# Mutli-Stepper-Driver_Rev_2.net
KiCad netlist of a schematic drawn in EAGLE
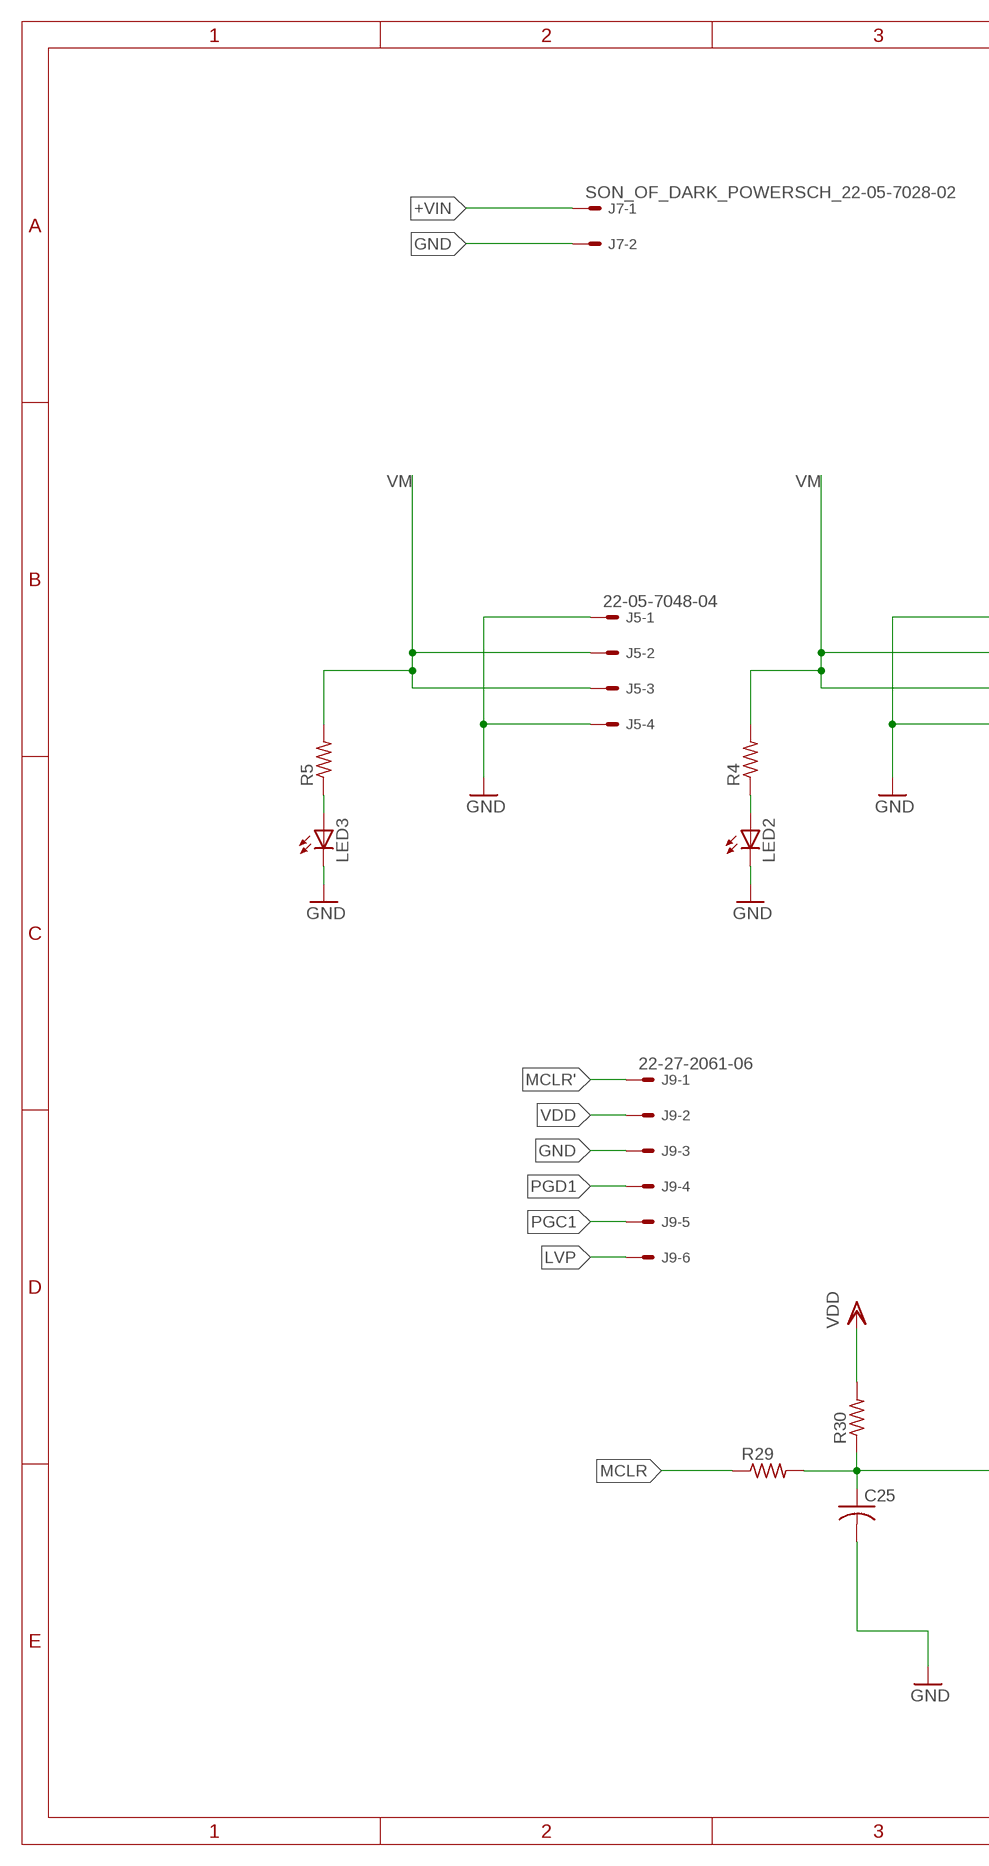
[diagram p0: schematic, sheet 1, part 1 of 2]
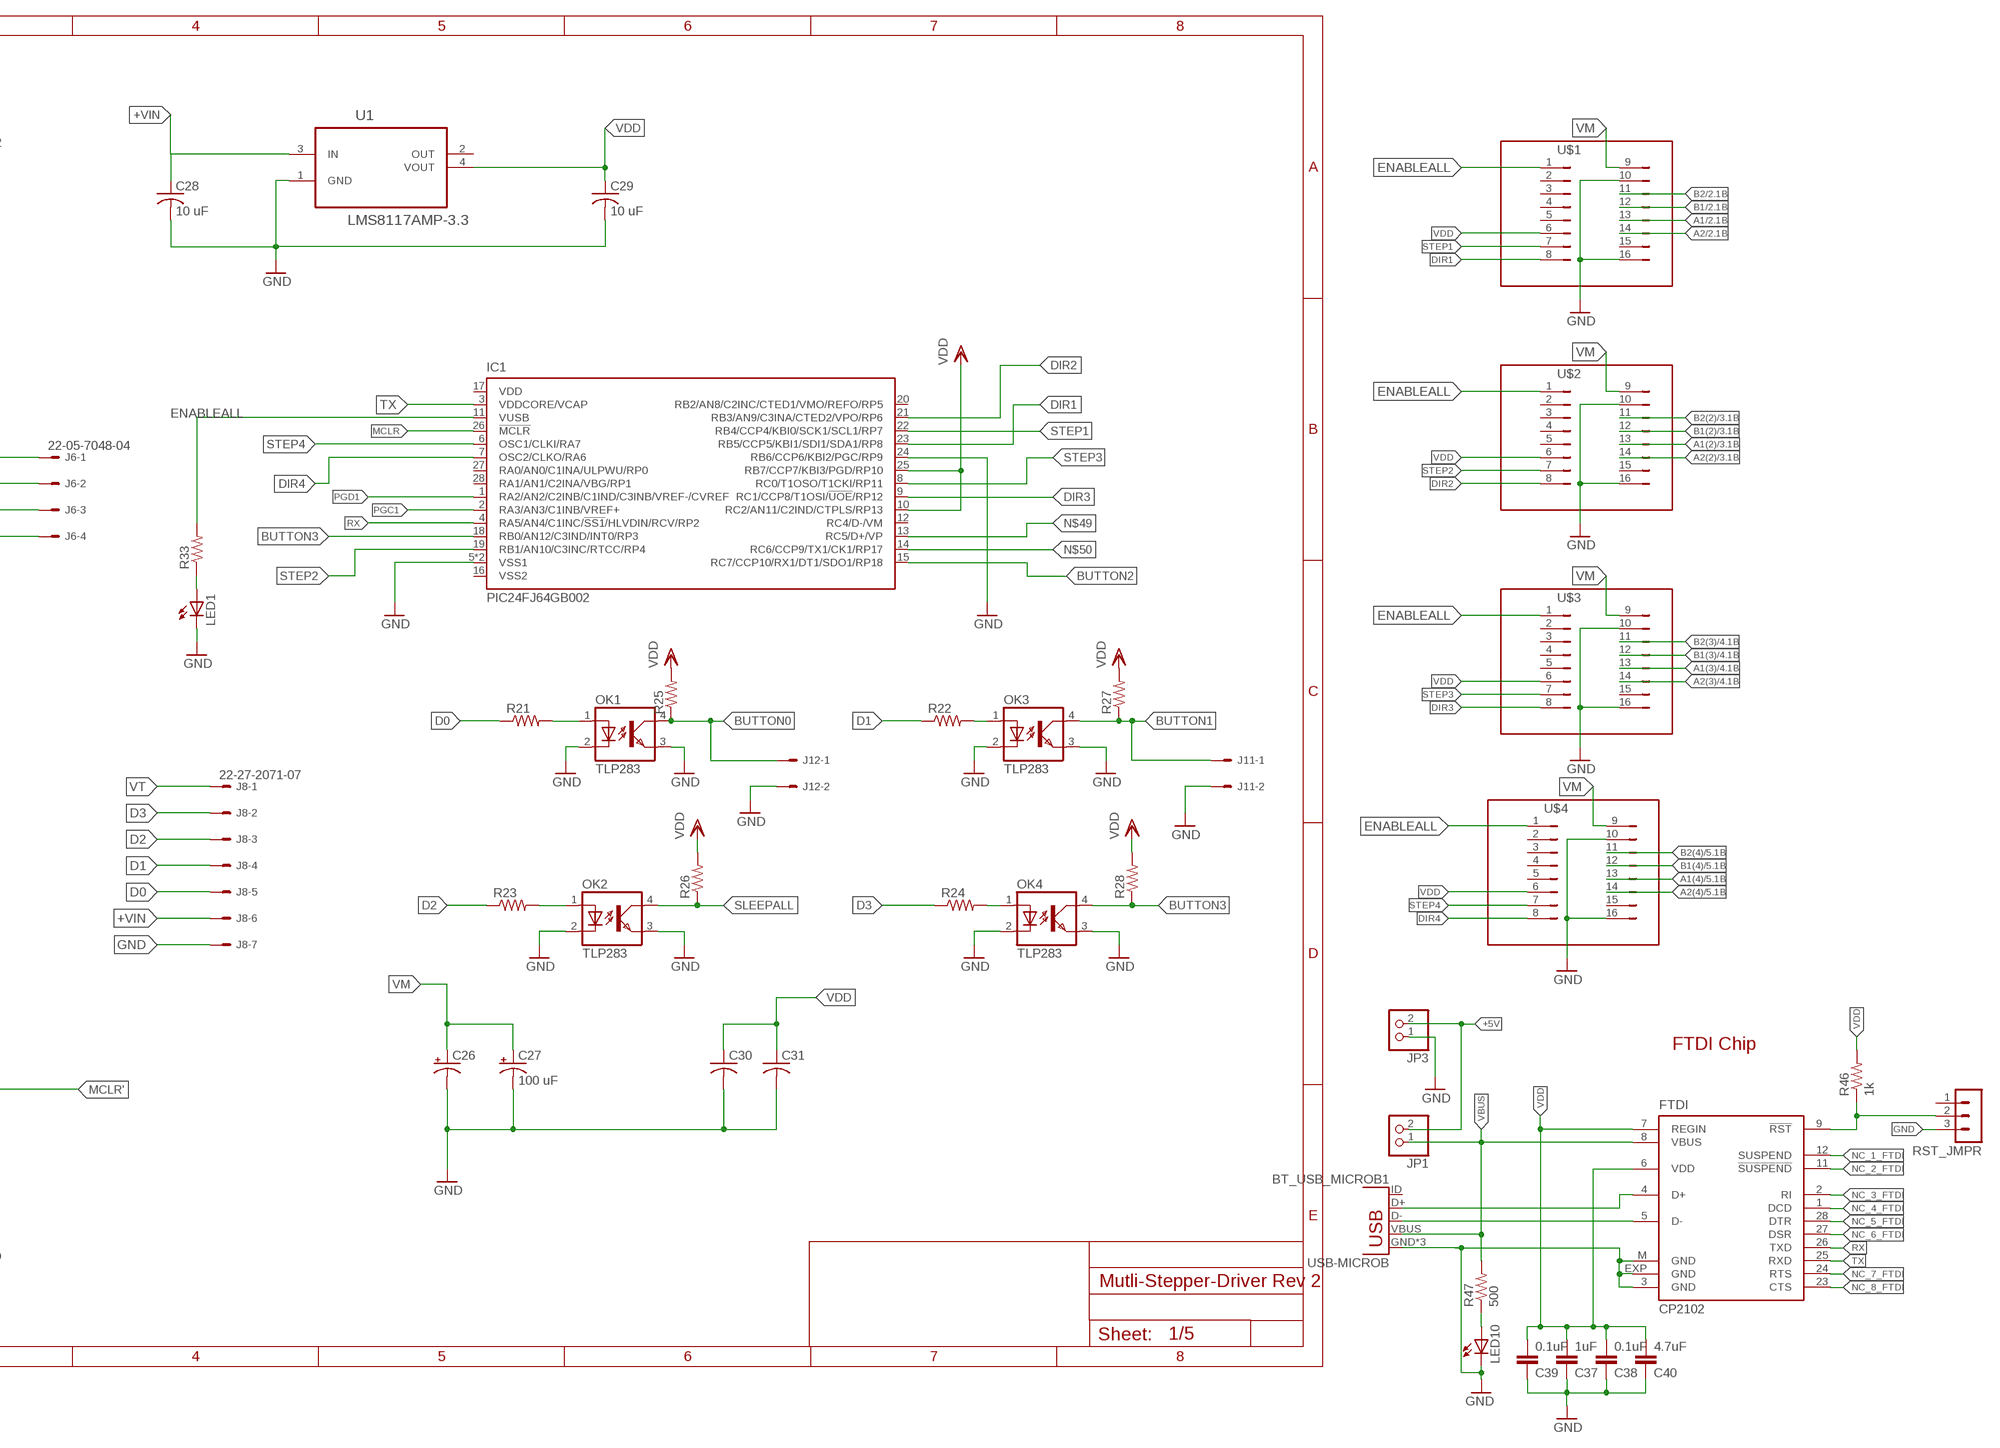
[diagram p1: schematic, sheet 1, part 2 of 2]
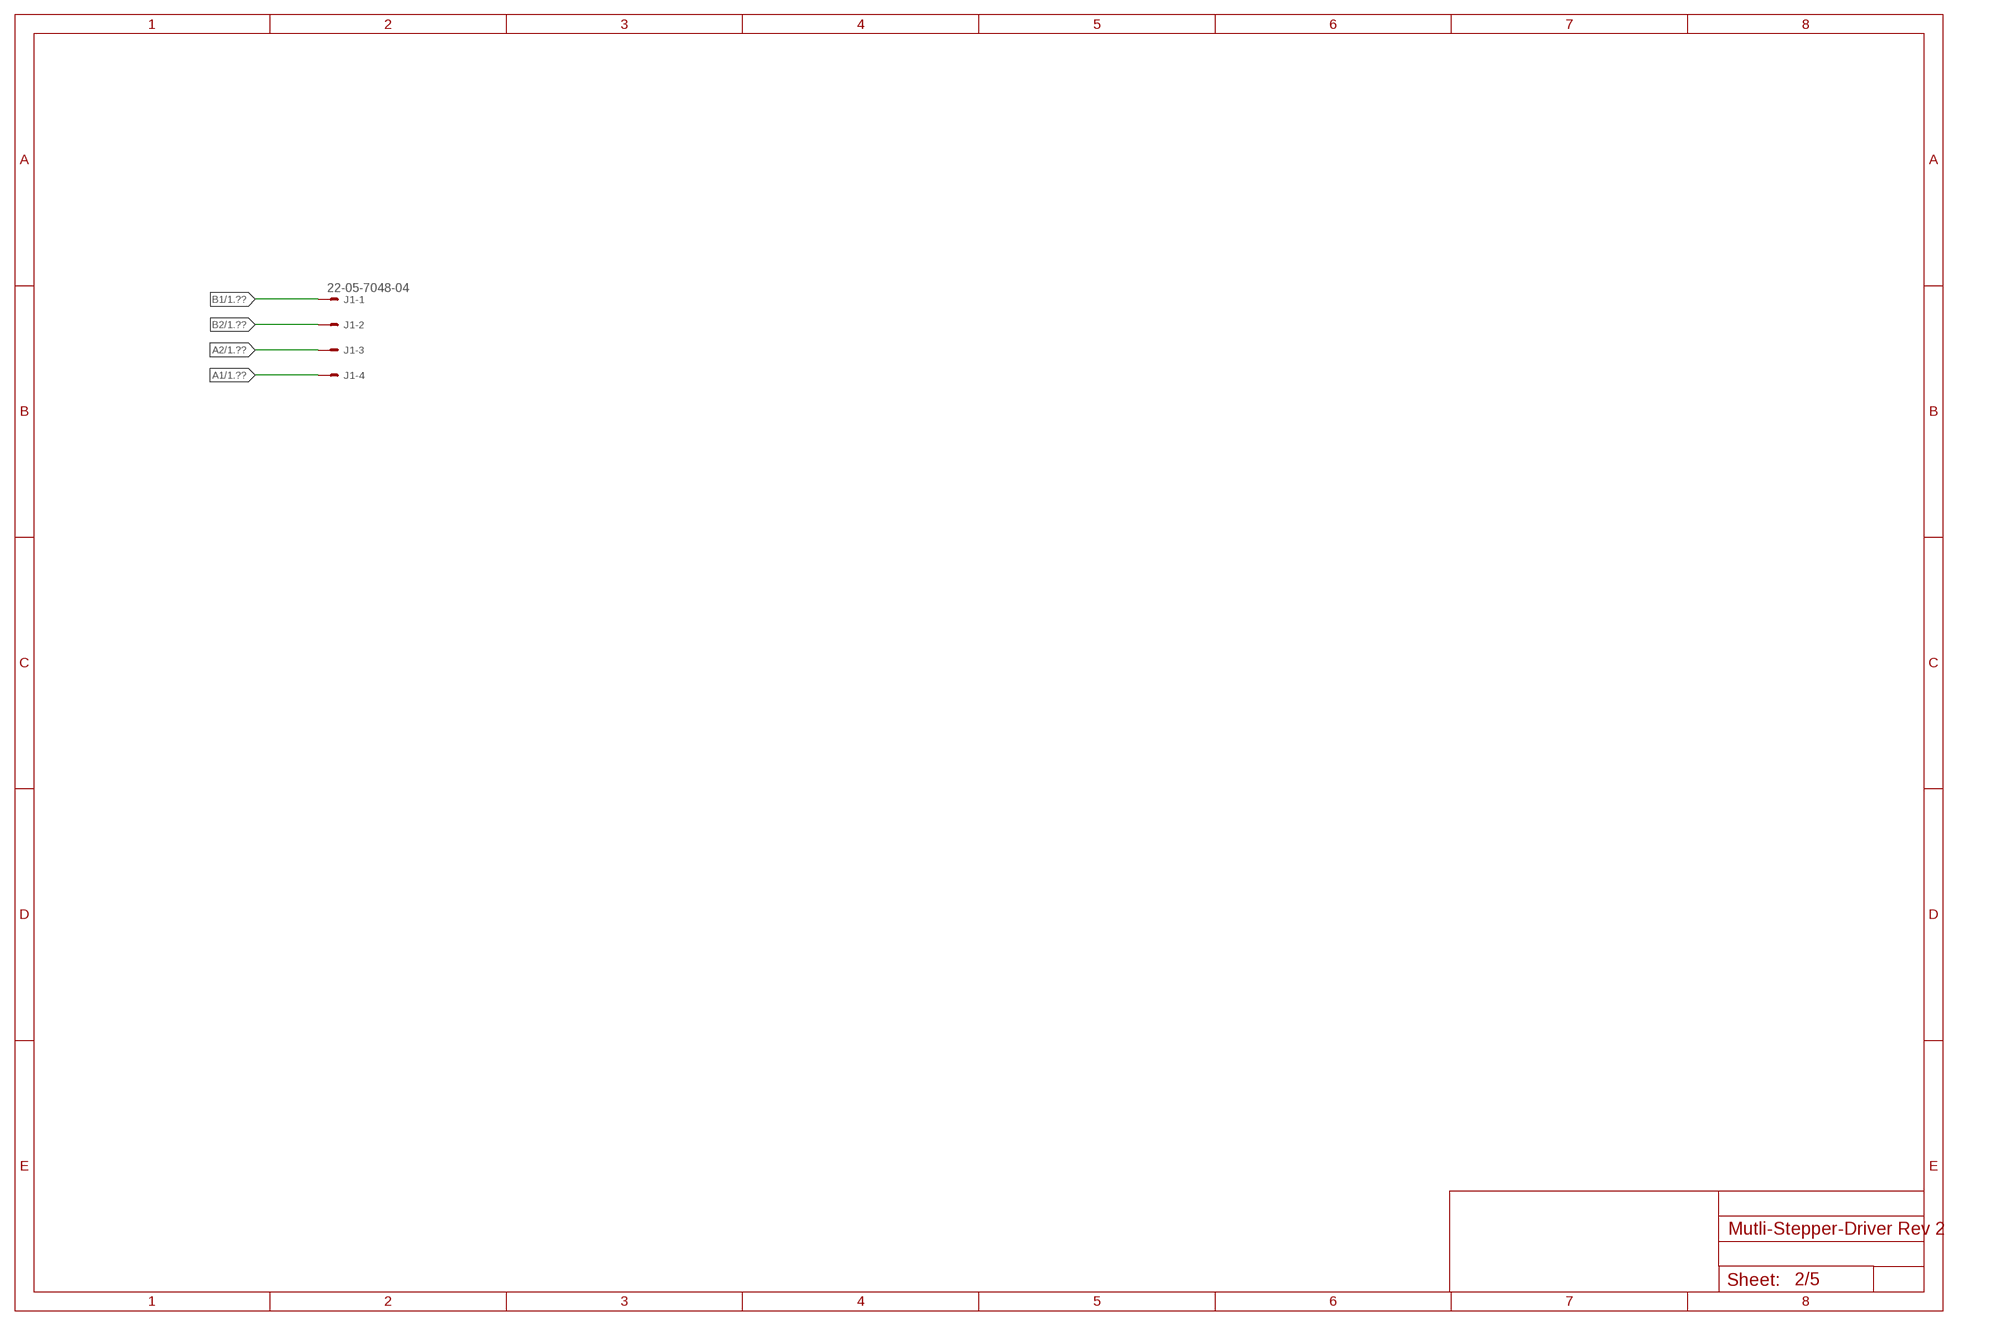
[diagram p2: schematic, sheet 2]
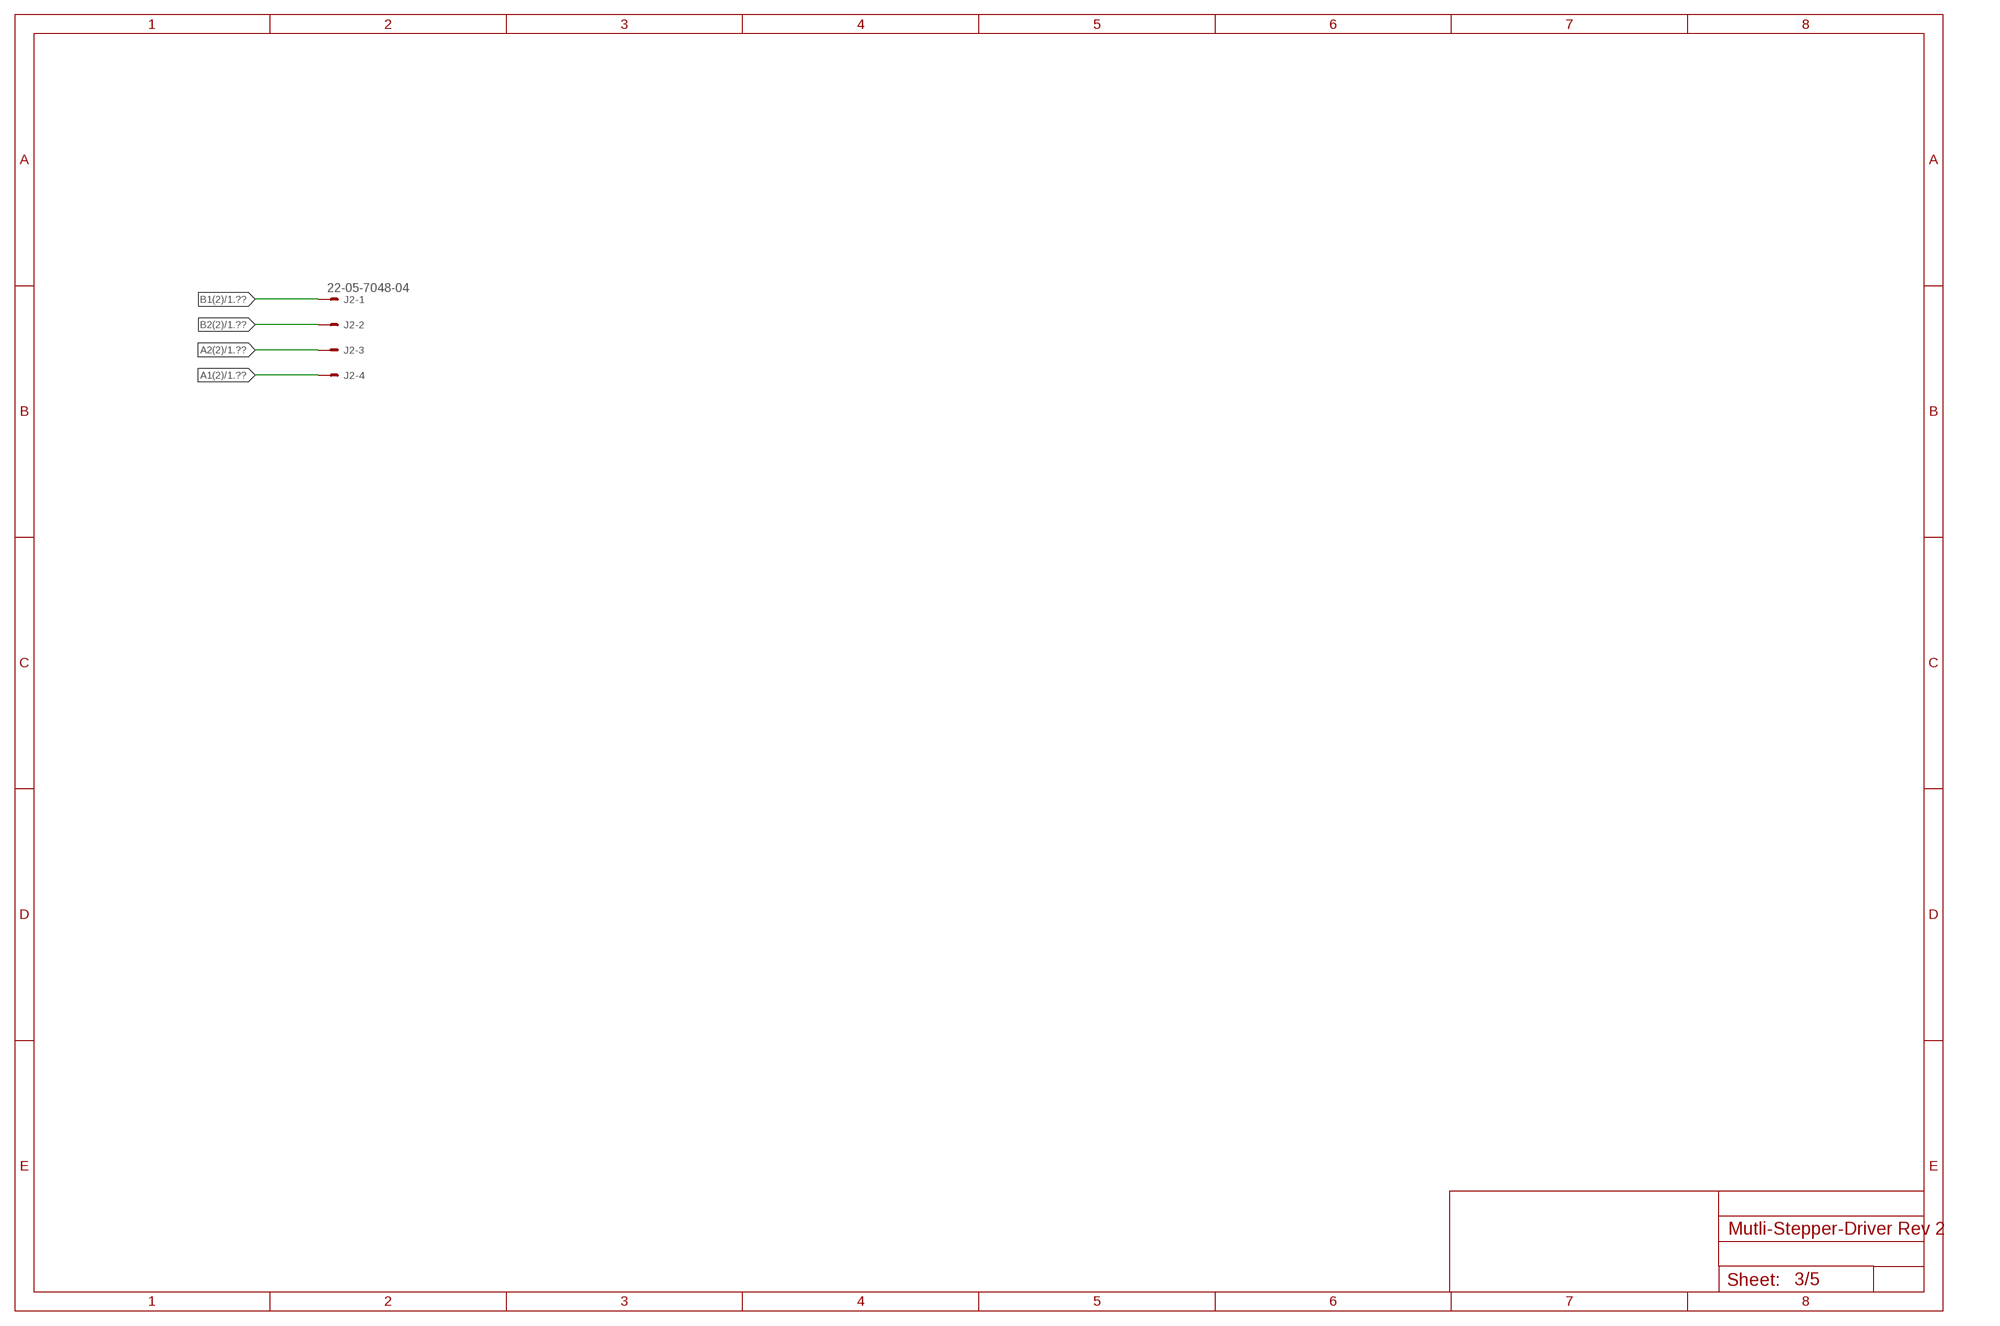
[diagram p3: schematic, sheet 3]
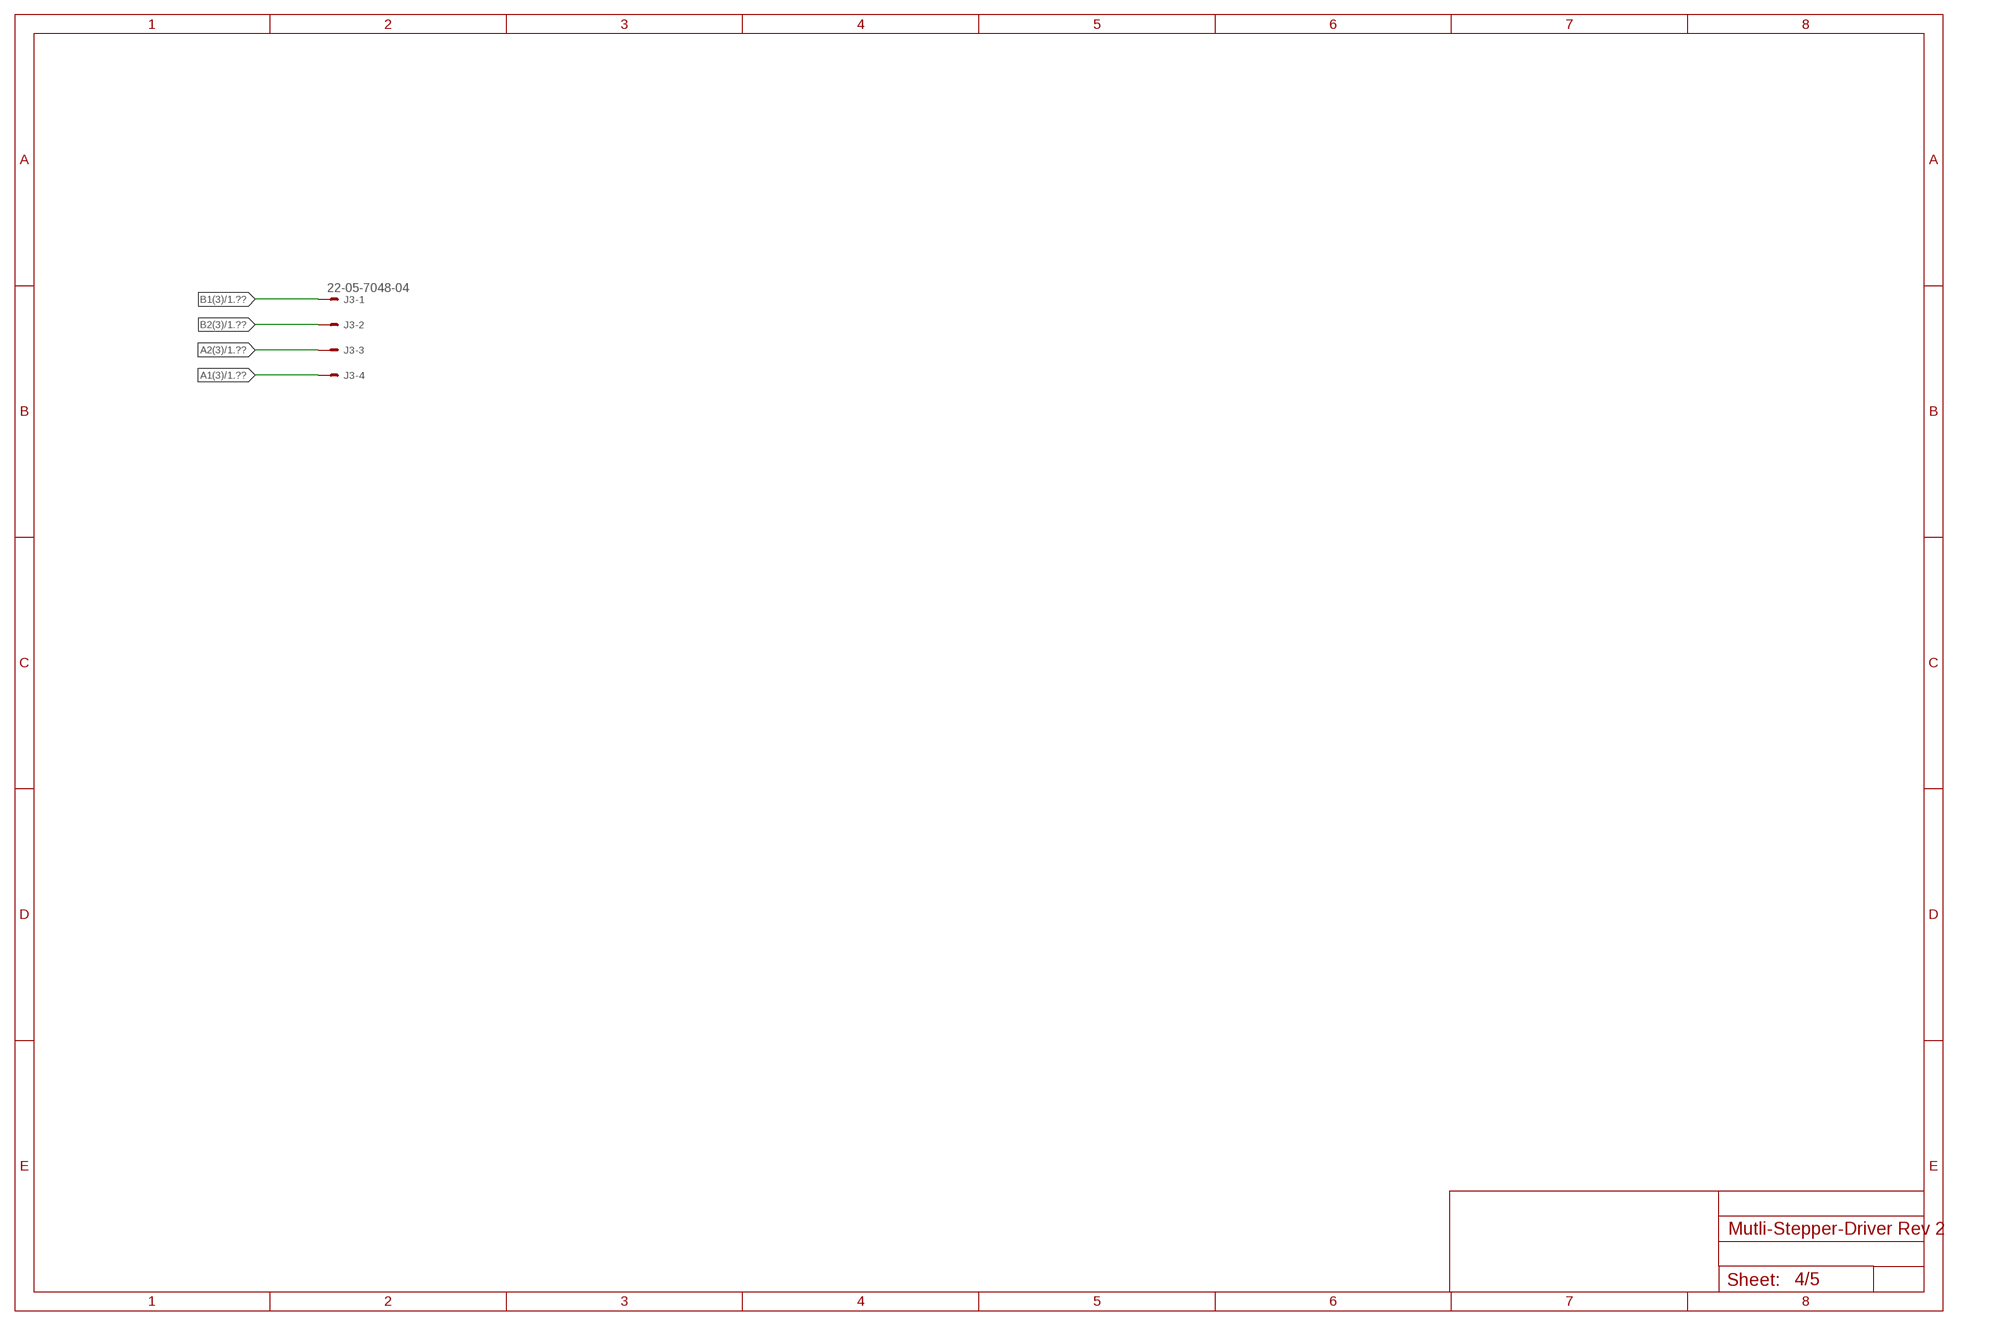
[diagram p4: schematic, sheet 4]
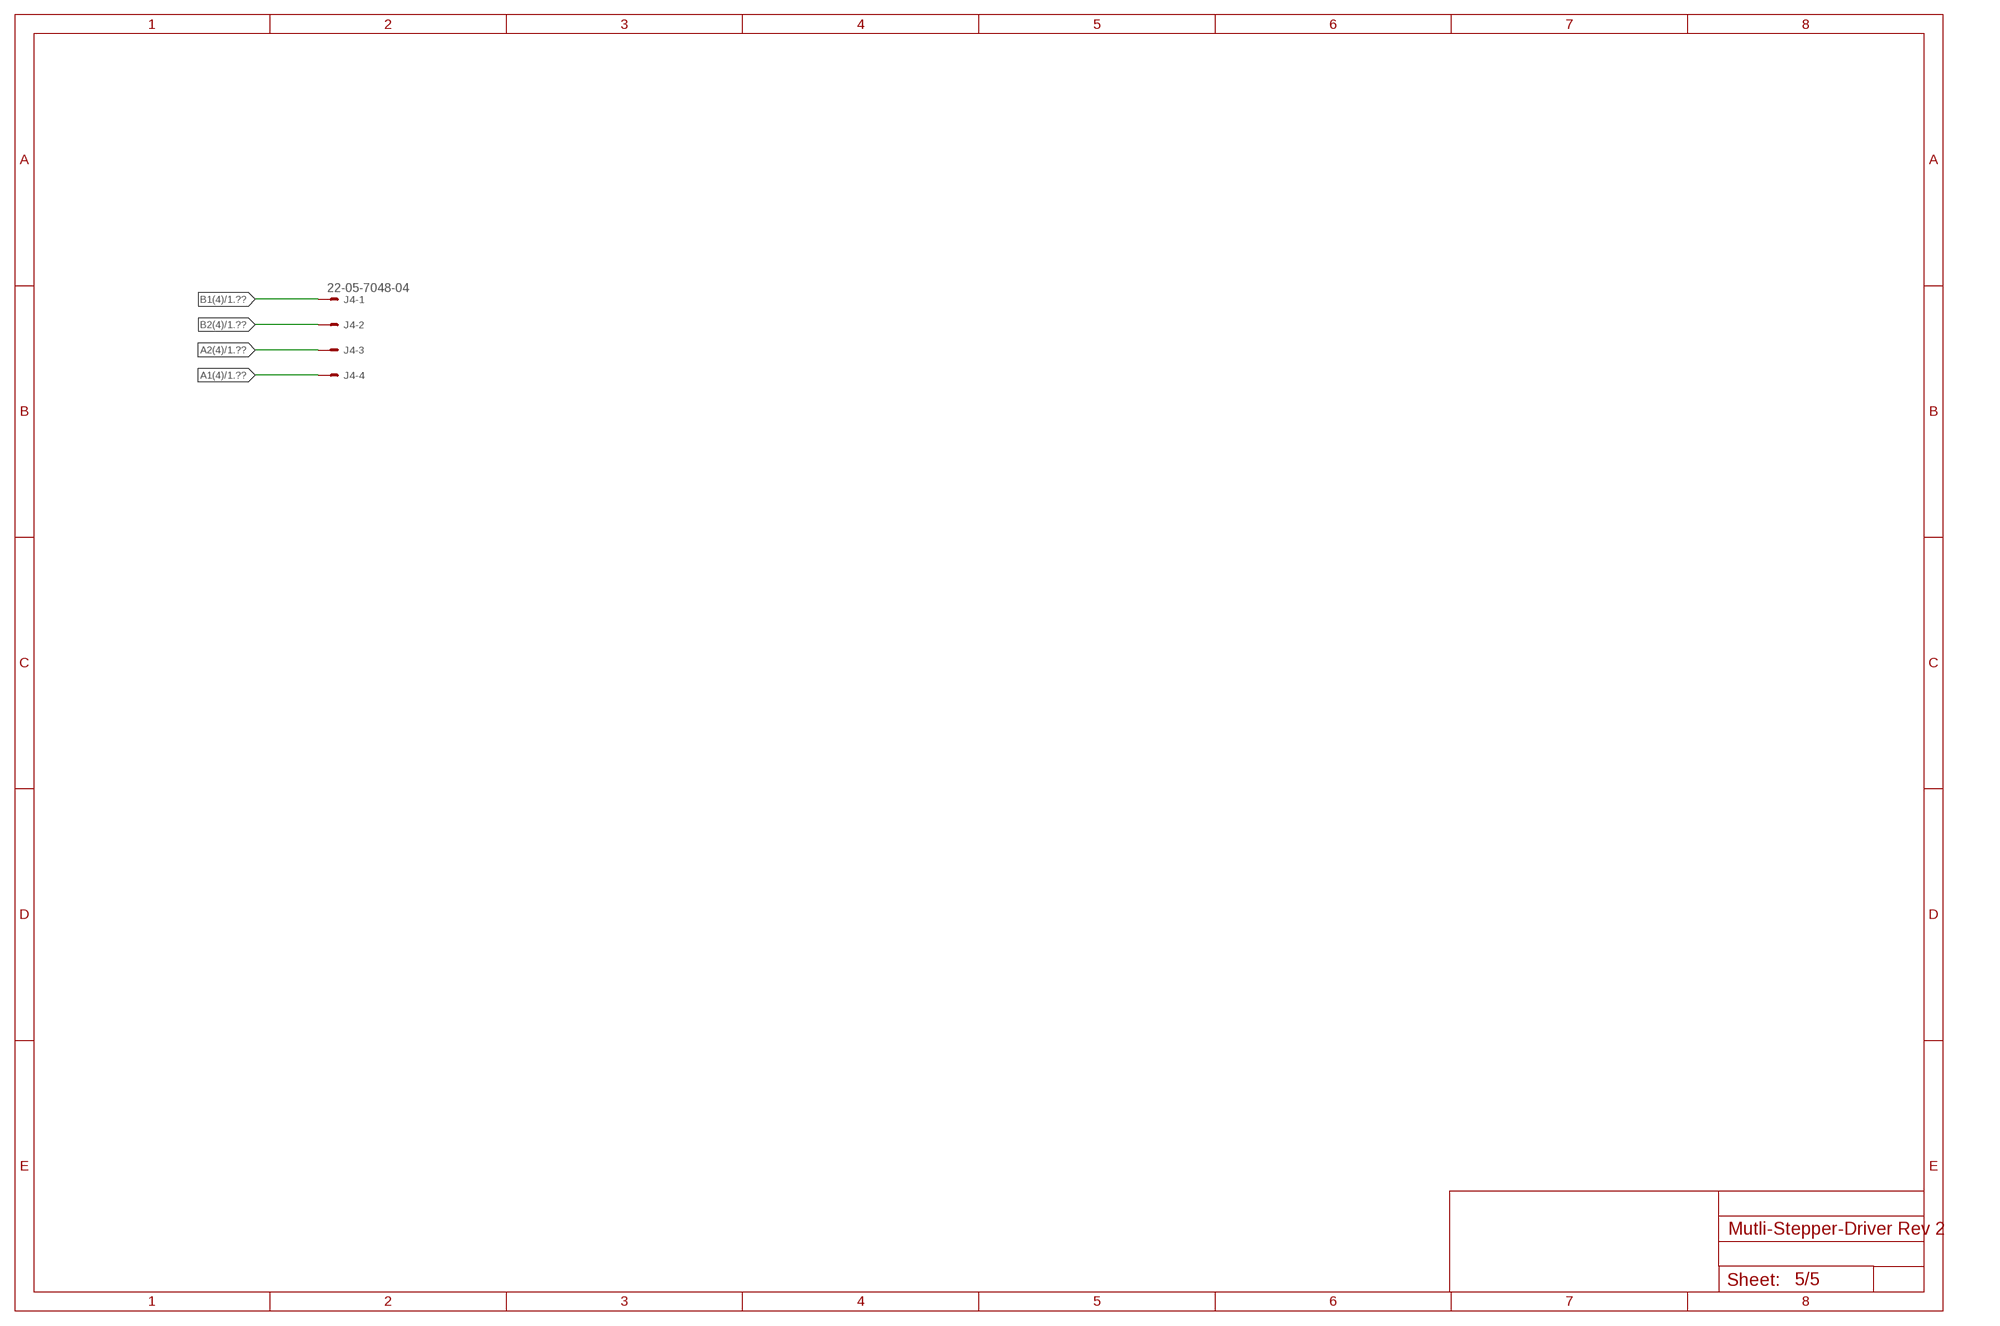
[diagram p5: schematic, sheet 5]

(export (version "E")
  (design (tool "Eeschema 10.0.6"))
  (components
    (comp (ref "BT_USB_MICROB1")
      (value "USB-MICROB")
      (footprint "eagle-import:USB-MICROB")
      (libsource (lib "eagle-import") (part "USB-MICROB"))
    )
    (comp (ref "C25")
      (value "C-USC0805")
      (footprint "eagle-import:C0805")
      (libsource (lib "eagle-import") (part "C-USC0805"))
    )
    (comp (ref "C26")
      (value "CPOL-USCT7343")
      (footprint "eagle-import:CT7343")
      (libsource (lib "eagle-import") (part "CPOL-USCT7343"))
    )
    (comp (ref "C27")
      (value "100 uF")
      (footprint "eagle-import:CT7343")
      (libsource (lib "eagle-import") (part "CPOL-USCT7343"))
    )
    (comp (ref "C28")
      (value "10 uF")
      (footprint "eagle-import:C3216")
      (libsource (lib "eagle-import") (part "C-USC3216"))
    )
    (comp (ref "C29")
      (value "10 uF")
      (footprint "eagle-import:C3216")
      (libsource (lib "eagle-import") (part "C-USC3216"))
    )
    (comp (ref "C30")
      (value "C-USC0805")
      (footprint "eagle-import:C0805")
      (libsource (lib "eagle-import") (part "C-USC0805"))
    )
    (comp (ref "C31")
      (value "C-USC0805")
      (footprint "eagle-import:C0805")
      (libsource (lib "eagle-import") (part "C-USC0805"))
    )
    (comp (ref "C37")
      (value "1uF")
      (footprint "eagle-import:C0805")
      (libsource (lib "eagle-import") (part "C-EUC0805"))
    )
    (comp (ref "C38")
      (value "0.1uF")
      (footprint "eagle-import:C0805")
      (libsource (lib "eagle-import") (part "C-EUC0805"))
    )
    (comp (ref "C39")
      (value "0.1uF")
      (footprint "eagle-import:C0805")
      (libsource (lib "eagle-import") (part "C-EUC0805"))
    )
    (comp (ref "C40")
      (value "4.7uF")
      (footprint "eagle-import:C0805")
      (libsource (lib "eagle-import") (part "C-EUC0805"))
    )
    (comp (ref "FTDI")
      (value "CP2102")
      (footprint "eagle-import:MLP28")
      (fields (field (name "MF") "FARNELL") (field (name "MPN") "CP2102-GM"))
      (libsource (lib "eagle-import") (part "CP2102"))
    )
    (comp (ref "IC1")
      (value "PIC24FJ64GB002")
      (footprint "eagle-import:MICROCHIP_QFN28-ML_6X6MM")
      (libsource (lib "eagle-import") (part "MICROCHIP_PIC18F2J53ML"))
    )
    (comp (ref "J5")
      (value "22-05-7048-04")
      (footprint "eagle-import:7395-04")
      (libsource (lib "eagle-import") (part "22-?-0405-7048"))
    )
    (comp (ref "J6")
      (value "22-05-7048-04")
      (footprint "eagle-import:7395-04")
      (libsource (lib "eagle-import") (part "22-?-0405-7048"))
    )
    (comp (ref "J7")
      (value "SON_OF_DARK_POWERSCH_22-05-7028-02")
      (footprint "eagle-import:SON_OF_DARK_POWERSCH_7395-02")
      (libsource (lib "eagle-import") (part "SON_OF_DARK_POWERSCH_22-?-0205-7028"))
    )
    (comp (ref "J8")
      (value "22-27-2071-07")
      (footprint "eagle-import:6410-07")
      (libsource (lib "eagle-import") (part "22-?-0727-2071"))
    )
    (comp (ref "J9")
      (value "22-27-2061-06")
      (footprint "eagle-import:6410-06")
      (libsource (lib "eagle-import") (part "22-?-0627-2061"))
    )
    (comp (ref "J11")
      (value "SON_OF_DARK_POWERSCH_22-05-7028-02")
      (footprint "eagle-import:SON_OF_DARK_POWERSCH_7395-02")
      (libsource (lib "eagle-import") (part "SON_OF_DARK_POWERSCH_22-?-0205-7028"))
    )
    (comp (ref "J12")
      (value "SON_OF_DARK_POWERSCH_22-05-7028-02")
      (footprint "eagle-import:SON_OF_DARK_POWERSCH_7395-02")
      (libsource (lib "eagle-import") (part "SON_OF_DARK_POWERSCH_22-?-0205-7028"))
    )
    (comp (ref "JP1")
      (value "PINHD-1X2")
      (footprint "eagle-import:1X02")
      (libsource (lib "eagle-import") (part "PINHD-1X2"))
    )
    (comp (ref "JP3")
      (value "PINHD-1X2")
      (footprint "eagle-import:1X02")
      (libsource (lib "eagle-import") (part "PINHD-1X2"))
    )
    (comp (ref "LED1")
      (value "LEDCHIPLED_0805")
      (footprint "eagle-import:CHIPLED_0805")
      (libsource (lib "eagle-import") (part "led_LEDCHIPLED_0805"))
    )
    (comp (ref "LED2")
      (value "LEDCHIPLED_0805")
      (footprint "eagle-import:CHIPLED_0805")
      (libsource (lib "eagle-import") (part "led_LEDCHIPLED_0805"))
    )
    (comp (ref "LED3")
      (value "LEDCHIPLED_0805")
      (footprint "eagle-import:CHIPLED_0805")
      (libsource (lib "eagle-import") (part "led_LEDCHIPLED_0805"))
    )
    (comp (ref "LED10")
      (value "LEDSML0603")
      (footprint "eagle-import:SML0603")
      (libsource (lib "eagle-import") (part "LEDSML0603"))
    )
    (comp (ref "OK1")
      (value "TLP283")
      (footprint "eagle-import:MINI-FLAT-4")
      (libsource (lib "eagle-import") (part "TLP283"))
    )
    (comp (ref "OK2")
      (value "TLP283")
      (footprint "eagle-import:MINI-FLAT-4")
      (libsource (lib "eagle-import") (part "TLP283"))
    )
    (comp (ref "OK3")
      (value "TLP283")
      (footprint "eagle-import:MINI-FLAT-4")
      (libsource (lib "eagle-import") (part "TLP283"))
    )
    (comp (ref "OK4")
      (value "TLP283")
      (footprint "eagle-import:MINI-FLAT-4")
      (libsource (lib "eagle-import") (part "TLP283"))
    )
    (comp (ref "R4")
      (value "R-US_R0805")
      (footprint "eagle-import:R0805")
      (libsource (lib "eagle-import") (part "R-US_R0805"))
    )
    (comp (ref "R5")
      (value "R-US_R0805")
      (footprint "eagle-import:R0805")
      (libsource (lib "eagle-import") (part "R-US_R0805"))
    )
    (comp (ref "R21")
      (value "R-US_R0805")
      (footprint "eagle-import:R0805")
      (libsource (lib "eagle-import") (part "R-US_R0805"))
    )
    (comp (ref "R22")
      (value "R-US_R0805")
      (footprint "eagle-import:R0805")
      (libsource (lib "eagle-import") (part "R-US_R0805"))
    )
    (comp (ref "R23")
      (value "R-US_R0805")
      (footprint "eagle-import:R0805")
      (libsource (lib "eagle-import") (part "R-US_R0805"))
    )
    (comp (ref "R24")
      (value "R-US_R0805")
      (footprint "eagle-import:R0805")
      (libsource (lib "eagle-import") (part "R-US_R0805"))
    )
    (comp (ref "R25")
      (value "R-US_R0805")
      (footprint "eagle-import:R0805")
      (libsource (lib "eagle-import") (part "R-US_R0805"))
    )
    (comp (ref "R26")
      (value "R-US_R0805")
      (footprint "eagle-import:R0805")
      (libsource (lib "eagle-import") (part "R-US_R0805"))
    )
    (comp (ref "R27")
      (value "R-US_R0805")
      (footprint "eagle-import:R0805")
      (libsource (lib "eagle-import") (part "R-US_R0805"))
    )
    (comp (ref "R28")
      (value "R-US_R0805")
      (footprint "eagle-import:R0805")
      (libsource (lib "eagle-import") (part "R-US_R0805"))
    )
    (comp (ref "R29")
      (value "R-US_R0805")
      (footprint "eagle-import:R0805")
      (libsource (lib "eagle-import") (part "R-US_R0805"))
    )
    (comp (ref "R30")
      (value "R-US_R0805")
      (footprint "eagle-import:R0805")
      (libsource (lib "eagle-import") (part "R-US_R0805"))
    )
    (comp (ref "R33")
      (value "R-US_R0805")
      (footprint "eagle-import:R0805")
      (libsource (lib "eagle-import") (part "R-US_R0805"))
    )
    (comp (ref "R46")
      (value "1k")
      (footprint "eagle-import:R0805")
      (libsource (lib "eagle-import") (part "resistor_R-US_R0805"))
    )
    (comp (ref "R47")
      (value "500")
      (footprint "eagle-import:R0805")
      (libsource (lib "eagle-import") (part "resistor_R-US_R0805"))
    )
    (comp (ref "RST_JMPR")
      (value "MA03-1")
      (footprint "eagle-import:MA03-1")
      (libsource (lib "eagle-import") (part "MA03-1"))
    )
    (comp (ref "U$1")
      (value "DRIVER")
      (footprint "eagle-import:6410-08")
      (libsource (lib "eagle-import") (part "DRIVER"))
    )
    (comp (ref "U$2")
      (value "DRIVER")
      (footprint "eagle-import:6410-08")
      (libsource (lib "eagle-import") (part "DRIVER"))
    )
    (comp (ref "U$3")
      (value "DRIVER")
      (footprint "eagle-import:6410-08")
      (libsource (lib "eagle-import") (part "DRIVER"))
    )
    (comp (ref "U$4")
      (value "DRIVER")
      (footprint "eagle-import:6410-08")
      (libsource (lib "eagle-import") (part "DRIVER"))
    )
    (comp (ref "U1")
      (value "LMS8117AMP-3.3")
      (footprint "eagle-import:NSC-LMS8117AMP_SOT230P696X180-4N")
      (libsource (lib "eagle-import") (part "NSC-LMS8117AMP_LMS8117AMP-3.3"))
    )
    (comp (ref "J2")
      (value "22-05-7048-04")
      (footprint "eagle-import:7395-04")
      (libsource (lib "eagle-import") (part "22-?-0405-7048"))
    )
    (comp (ref "J1")
      (value "22-05-7048-04")
      (footprint "eagle-import:7395-04")
      (libsource (lib "eagle-import") (part "22-?-0405-7048"))
    )
    (comp (ref "J4")
      (value "22-05-7048-04")
      (footprint "eagle-import:7395-04")
      (libsource (lib "eagle-import") (part "22-?-0405-7048"))
    )
    (comp (ref "J3")
      (value "22-05-7048-04")
      (footprint "eagle-import:7395-04")
      (libsource (lib "eagle-import") (part "22-?-0405-7048"))
    )
  )
  (nets
    (net (code "1") (name "+5V") (class "Default")
      (node (ref "JP1") (pin "2") (pinfunction "2_2") (pintype "passive"))
      (node (ref "JP3") (pin "2") (pinfunction "2_2") (pintype "passive"))
    )
    (net (code "2") (name "+VIN") (class "Default")
      (node (ref "C28") (pin "1") (pinfunction "1_1") (pintype "passive"))
      (node (ref "J7") (pin "1") (pinfunction "S_1") (pintype "passive"))
      (node (ref "J8") (pin "6") (pinfunction "S_6") (pintype "passive"))
      (node (ref "U1") (pin "3") (pinfunction "IN_3") (pintype "power_in"))
    )
    (net (code "3") (name "A1") (class "Default")
      (node (ref "J1") (pin "4") (pinfunction "S_4") (pintype "passive"))
      (node (ref "U$1") (pin "13") (pinfunction "13_13") (pintype "passive"))
    )
    (net (code "4") (name "A1(2)") (class "Default")
      (node (ref "J2") (pin "4") (pinfunction "S_4") (pintype "passive"))
      (node (ref "U$2") (pin "13") (pinfunction "13_13") (pintype "passive"))
    )
    (net (code "5") (name "A1(3)") (class "Default")
      (node (ref "J3") (pin "4") (pinfunction "S_4") (pintype "passive"))
      (node (ref "U$3") (pin "13") (pinfunction "13_13") (pintype "passive"))
    )
    (net (code "6") (name "A1(4)") (class "Default")
      (node (ref "J4") (pin "4") (pinfunction "S_4") (pintype "passive"))
      (node (ref "U$4") (pin "13") (pinfunction "13_13") (pintype "passive"))
    )
    (net (code "7") (name "A2") (class "Default")
      (node (ref "J1") (pin "3") (pinfunction "S_3") (pintype "passive"))
      (node (ref "U$1") (pin "14") (pinfunction "14_14") (pintype "passive"))
    )
    (net (code "8") (name "A2(2)") (class "Default")
      (node (ref "J2") (pin "3") (pinfunction "S_3") (pintype "passive"))
      (node (ref "U$2") (pin "14") (pinfunction "14_14") (pintype "passive"))
    )
    (net (code "9") (name "A2(3)") (class "Default")
      (node (ref "J3") (pin "3") (pinfunction "S_3") (pintype "passive"))
      (node (ref "U$3") (pin "14") (pinfunction "14_14") (pintype "passive"))
    )
    (net (code "10") (name "A2(4)") (class "Default")
      (node (ref "J4") (pin "3") (pinfunction "S_3") (pintype "passive"))
      (node (ref "U$4") (pin "14") (pinfunction "14_14") (pintype "passive"))
    )
    (net (code "11") (name "B1") (class "Default")
      (node (ref "J1") (pin "1") (pinfunction "S_1") (pintype "passive"))
      (node (ref "U$1") (pin "12") (pinfunction "12_12") (pintype "passive"))
    )
    (net (code "12") (name "B1(2)") (class "Default")
      (node (ref "J2") (pin "1") (pinfunction "S_1") (pintype "passive"))
      (node (ref "U$2") (pin "12") (pinfunction "12_12") (pintype "passive"))
    )
    (net (code "13") (name "B1(3)") (class "Default")
      (node (ref "J3") (pin "1") (pinfunction "S_1") (pintype "passive"))
      (node (ref "U$3") (pin "12") (pinfunction "12_12") (pintype "passive"))
    )
    (net (code "14") (name "B1(4)") (class "Default")
      (node (ref "J4") (pin "1") (pinfunction "S_1") (pintype "passive"))
      (node (ref "U$4") (pin "12") (pinfunction "12_12") (pintype "passive"))
    )
    (net (code "15") (name "B2") (class "Default")
      (node (ref "J1") (pin "2") (pinfunction "S_2") (pintype "passive"))
      (node (ref "U$1") (pin "11") (pinfunction "11_11") (pintype "passive"))
    )
    (net (code "16") (name "B2(2)") (class "Default")
      (node (ref "J2") (pin "2") (pinfunction "S_2") (pintype "passive"))
      (node (ref "U$2") (pin "11") (pinfunction "11_11") (pintype "passive"))
    )
    (net (code "17") (name "B2(3)") (class "Default")
      (node (ref "J3") (pin "2") (pinfunction "S_2") (pintype "passive"))
      (node (ref "U$3") (pin "11") (pinfunction "11_11") (pintype "passive"))
    )
    (net (code "18") (name "B2(4)") (class "Default")
      (node (ref "J4") (pin "2") (pinfunction "S_2") (pintype "passive"))
      (node (ref "U$4") (pin "11") (pinfunction "11_11") (pintype "passive"))
    )
    (net (code "19") (name "BUTTON0") (class "Default")
      (node (ref "J12") (pin "1") (pinfunction "S_1") (pintype "passive"))
      (node (ref "OK1") (pin "4") (pinfunction "COL_4") (pintype "passive"))
      (node (ref "R25") (pin "1") (pinfunction "1_1") (pintype "passive"))
    )
    (net (code "20") (name "BUTTON1") (class "Default")
      (node (ref "J11") (pin "1") (pinfunction "S_1") (pintype "passive"))
      (node (ref "OK3") (pin "4") (pinfunction "COL_4") (pintype "passive"))
      (node (ref "R27") (pin "1") (pinfunction "1_1") (pintype "passive"))
    )
    (net (code "21") (name "BUTTON2") (class "Default")
      (node (ref "IC1") (pin "15") (pinfunction "RC7/CCP10/RX1/DT1/SDO1/RP18_15") (pintype "bidirectional"))
    )
    (net (code "22") (name "BUTTON3") (class "Default")
      (node (ref "IC1") (pin "18") (pinfunction "RB0/AN12/C3IND/INT0/RP3_18") (pintype "bidirectional"))
      (node (ref "OK4") (pin "4") (pinfunction "COL_4") (pintype "passive"))
      (node (ref "R28") (pin "1") (pinfunction "1_1") (pintype "passive"))
    )
    (net (code "23") (name "D0") (class "Default")
      (node (ref "J8") (pin "5") (pinfunction "S_5") (pintype "passive"))
      (node (ref "R21") (pin "1") (pinfunction "1_1") (pintype "passive"))
    )
    (net (code "24") (name "D1") (class "Default")
      (node (ref "J8") (pin "4") (pinfunction "S_4") (pintype "passive"))
      (node (ref "R22") (pin "1") (pinfunction "1_1") (pintype "passive"))
    )
    (net (code "25") (name "D2") (class "Default")
      (node (ref "J8") (pin "3") (pinfunction "S_3") (pintype "passive"))
      (node (ref "R23") (pin "1") (pinfunction "1_1") (pintype "passive"))
    )
    (net (code "26") (name "D3") (class "Default")
      (node (ref "J8") (pin "2") (pinfunction "S_2") (pintype "passive"))
      (node (ref "R24") (pin "1") (pinfunction "1_1") (pintype "passive"))
    )
    (net (code "27") (name "DIR1") (class "Default")
      (node (ref "IC1") (pin "23") (pinfunction "RB5/CCP5/KBI1/SDI1/SDA1/RP8_23") (pintype "bidirectional"))
      (node (ref "U$1") (pin "8") (pinfunction "8_8") (pintype "passive"))
    )
    (net (code "28") (name "DIR2") (class "Default")
      (node (ref "IC1") (pin "21") (pinfunction "RB3/AN9/C3INA/CTED2/VPO/RP6_21") (pintype "bidirectional"))
      (node (ref "U$2") (pin "8") (pinfunction "8_8") (pintype "passive"))
    )
    (net (code "29") (name "DIR3") (class "Default")
      (node (ref "IC1") (pin "9") (pinfunction "RC1/CCP8/T1OSI/~{UOE}/RP12_9") (pintype "bidirectional"))
      (node (ref "U$3") (pin "8") (pinfunction "8_8") (pintype "passive"))
    )
    (net (code "30") (name "DIR4") (class "Default")
      (node (ref "IC1") (pin "7") (pinfunction "OSC2/CLKO/RA6_7") (pintype "bidirectional"))
      (node (ref "U$4") (pin "8") (pinfunction "8_8") (pintype "passive"))
    )
    (net (code "31") (name "ENABLEALL") (class "Default")
      (node (ref "IC1") (pin "11") (pinfunction "VUSB_11") (pintype "input"))
      (node (ref "R33") (pin "2") (pinfunction "2_2") (pintype "passive"))
      (node (ref "U$1") (pin "1") (pinfunction "1_1") (pintype "passive"))
      (node (ref "U$2") (pin "1") (pinfunction "1_1") (pintype "passive"))
      (node (ref "U$3") (pin "1") (pinfunction "1_1") (pintype "passive"))
      (node (ref "U$4") (pin "1") (pinfunction "1_1") (pintype "passive"))
    )
    (net (code "32") (name "GND") (class "Default")
      (node (ref "BT_USB_MICROB1") (pin "GND") (pinfunction "GND_GND") (pintype "bidirectional"))
      (node (ref "BT_USB_MICROB1") (pin "MT1") (pinfunction "GND_MT1") (pintype "bidirectional"))
      (node (ref "BT_USB_MICROB1") (pin "MT2") (pinfunction "GND_MT2") (pintype "bidirectional"))
      (node (ref "C25") (pin "2") (pinfunction "2_2") (pintype "passive"))
      (node (ref "C26") (pin "-") (pinfunction "-_-") (pintype "passive"))
      (node (ref "C27") (pin "-") (pinfunction "-_-") (pintype "passive"))
      (node (ref "C28") (pin "2") (pinfunction "2_2") (pintype "passive"))
      (node (ref "C29") (pin "2") (pinfunction "2_2") (pintype "passive"))
      (node (ref "C30") (pin "2") (pinfunction "2_2") (pintype "passive"))
      (node (ref "C31") (pin "2") (pinfunction "2_2") (pintype "passive"))
      (node (ref "C37") (pin "1") (pinfunction "1_1") (pintype "passive"))
      (node (ref "C38") (pin "1") (pinfunction "1_1") (pintype "passive"))
      (node (ref "C39") (pin "1") (pinfunction "1_1") (pintype "passive"))
      (node (ref "C40") (pin "1") (pinfunction "1_1") (pintype "passive"))
      (node (ref "FTDI") (pin "3") (pinfunction "GND_3") (pintype "power_in"))
      (node (ref "FTDI") (pin "EXP") (pinfunction "GND_EXP") (pintype "power_in"))
      (node (ref "FTDI") (pin "M") (pinfunction "GND_M") (pintype "power_in"))
      (node (ref "IC1") (pin "24") (pinfunction "RB6/CCP6/KBI2/PGC/RP9_24") (pintype "bidirectional"))
      (node (ref "IC1") (pin "5") (pinfunction "VSS1_5") (pintype "input"))
      (node (ref "IC1") (pin "EXP") (pinfunction "VSS1_EXP") (pintype "input"))
      (node (ref "J11") (pin "2") (pinfunction "S_2") (pintype "passive"))
      (node (ref "J12") (pin "2") (pinfunction "S_2") (pintype "passive"))
      (node (ref "J5") (pin "1") (pinfunction "S_1") (pintype "passive"))
      (node (ref "J5") (pin "4") (pinfunction "S_4") (pintype "passive"))
      (node (ref "J6") (pin "1") (pinfunction "S_1") (pintype "passive"))
      (node (ref "J6") (pin "4") (pinfunction "S_4") (pintype "passive"))
      (node (ref "J7") (pin "2") (pinfunction "S_2") (pintype "passive"))
      (node (ref "J8") (pin "7") (pinfunction "S_7") (pintype "passive"))
      (node (ref "J9") (pin "3") (pinfunction "S_3") (pintype "passive"))
      (node (ref "JP3") (pin "1") (pinfunction "1_1") (pintype "passive"))
      (node (ref "LED1") (pin "C") (pinfunction "C_C") (pintype "passive"))
      (node (ref "LED10") (pin "C") (pinfunction "C_C") (pintype "passive"))
      (node (ref "LED2") (pin "C") (pinfunction "C_C") (pintype "passive"))
      (node (ref "LED3") (pin "C") (pinfunction "C_C") (pintype "passive"))
      (node (ref "OK1") (pin "2") (pinfunction "C_2") (pintype "passive"))
      (node (ref "OK1") (pin "3") (pinfunction "EMIT_3") (pintype "passive"))
      (node (ref "OK2") (pin "2") (pinfunction "C_2") (pintype "passive"))
      (node (ref "OK2") (pin "3") (pinfunction "EMIT_3") (pintype "passive"))
      (node (ref "OK3") (pin "2") (pinfunction "C_2") (pintype "passive"))
      (node (ref "OK3") (pin "3") (pinfunction "EMIT_3") (pintype "passive"))
      (node (ref "OK4") (pin "2") (pinfunction "C_2") (pintype "passive"))
      (node (ref "OK4") (pin "3") (pinfunction "EMIT_3") (pintype "passive"))
      (node (ref "RST_JMPR") (pin "3") (pinfunction "3_3") (pintype "passive"))
      (node (ref "U$1") (pin "10") (pinfunction "10_10") (pintype "passive"))
      (node (ref "U$1") (pin "16") (pinfunction "16_16") (pintype "passive"))
      (node (ref "U$2") (pin "10") (pinfunction "10_10") (pintype "passive"))
      (node (ref "U$2") (pin "16") (pinfunction "16_16") (pintype "passive"))
      (node (ref "U$3") (pin "10") (pinfunction "10_10") (pintype "passive"))
      (node (ref "U$3") (pin "16") (pinfunction "16_16") (pintype "passive"))
      (node (ref "U$4") (pin "10") (pinfunction "10_10") (pintype "passive"))
      (node (ref "U$4") (pin "16") (pinfunction "16_16") (pintype "passive"))
      (node (ref "U1") (pin "1") (pinfunction "GND_1") (pintype "passive"))
    )
    (net (code "33") (name "LVP") (class "Default")
      (node (ref "J9") (pin "6") (pinfunction "S_6") (pintype "passive"))
    )
    (net (code "34") (name "MCLR") (class "Default")
      (node (ref "IC1") (pin "26") (pinfunction "~{MCLR}_26") (pintype "input"))
      (node (ref "R29") (pin "1") (pinfunction "1_1") (pintype "passive"))
    )
    (net (code "35") (name "MCLR'") (class "Default")
      (node (ref "C25") (pin "1") (pinfunction "1_1") (pintype "passive"))
      (node (ref "J9") (pin "1") (pinfunction "S_1") (pintype "passive"))
      (node (ref "R29") (pin "2") (pinfunction "2_2") (pintype "passive"))
      (node (ref "R30") (pin "1") (pinfunction "1_1") (pintype "passive"))
    )
    (net (code "36") (name "N$49") (class "Default")
      (node (ref "IC1") (pin "13") (pinfunction "RC5/D+/VP_13") (pintype "bidirectional"))
    )
    (net (code "37") (name "N$50") (class "Default")
      (node (ref "IC1") (pin "14") (pinfunction "RC6/CCP9/TX1/CK1/RP17_14") (pintype "bidirectional"))
    )
    (net (code "38") (name "NC_1_FTDI") (class "Default")
      (node (ref "FTDI") (pin "12") (pinfunction "SUSPEND_12") (pintype "output"))
    )
    (net (code "39") (name "NC_2_FTDI") (class "Default")
      (node (ref "FTDI") (pin "11") (pinfunction "~{SUSPEND}_11") (pintype "output"))
    )
    (net (code "40") (name "NC_3_FTDI") (class "Default")
      (node (ref "FTDI") (pin "2") (pinfunction "RI_2") (pintype "input"))
    )
    (net (code "41") (name "NC_4_FTDI") (class "Default")
      (node (ref "FTDI") (pin "1") (pinfunction "DCD_1") (pintype "input"))
    )
    (net (code "42") (name "NC_5_FTDI") (class "Default")
      (node (ref "FTDI") (pin "28") (pinfunction "DTR_28") (pintype "output"))
    )
    (net (code "43") (name "NC_6_FTDI") (class "Default")
      (node (ref "FTDI") (pin "27") (pinfunction "DSR_27") (pintype "input"))
    )
    (net (code "44") (name "NC_7_FTDI") (class "Default")
      (node (ref "FTDI") (pin "24") (pinfunction "RTS_24") (pintype "output"))
    )
    (net (code "45") (name "NC_8_FTDI") (class "Default")
      (node (ref "FTDI") (pin "23") (pinfunction "CTS_23") (pintype "input"))
    )
    (net (code "46") (name "Net-(FTDI-D+)") (class "Default")
      (node (ref "BT_USB_MICROB1") (pin "D+") (pinfunction "D+_D+") (pintype "bidirectional"))
      (node (ref "FTDI") (pin "4") (pinfunction "D+_4") (pintype "bidirectional"))
    )
    (net (code "47") (name "Net-(FTDI-D-)") (class "Default")
      (node (ref "BT_USB_MICROB1") (pin "D-") (pinfunction "D-_D-") (pintype "bidirectional"))
      (node (ref "FTDI") (pin "5") (pinfunction "D-_5") (pintype "bidirectional"))
    )
    (net (code "48") (name "Net-(FTDI-~{RST})") (class "Default")
      (node (ref "FTDI") (pin "9") (pinfunction "~{RST}_9") (pintype "bidirectional"))
      (node (ref "R46") (pin "1") (pinfunction "1_1") (pintype "passive"))
      (node (ref "RST_JMPR") (pin "2") (pinfunction "2_2") (pintype "passive"))
    )
    (net (code "49") (name "Net-(LED1-PadA)") (class "Default")
      (node (ref "LED1") (pin "A") (pinfunction "A_A") (pintype "passive"))
      (node (ref "R33") (pin "1") (pinfunction "1_1") (pintype "passive"))
    )
    (net (code "50") (name "Net-(LED2-PadA)") (class "Default")
      (node (ref "LED2") (pin "A") (pinfunction "A_A") (pintype "passive"))
      (node (ref "R4") (pin "1") (pinfunction "1_1") (pintype "passive"))
    )
    (net (code "51") (name "Net-(LED3-PadA)") (class "Default")
      (node (ref "LED3") (pin "A") (pinfunction "A_A") (pintype "passive"))
      (node (ref "R5") (pin "1") (pinfunction "1_1") (pintype "passive"))
    )
    (net (code "52") (name "Net-(LED10-PadA)") (class "Default")
      (node (ref "LED10") (pin "A") (pinfunction "A_A") (pintype "passive"))
      (node (ref "R47") (pin "1") (pinfunction "1_1") (pintype "passive"))
    )
    (net (code "53") (name "Net-(OK1-A)") (class "Default")
      (node (ref "OK1") (pin "1") (pinfunction "A_1") (pintype "passive"))
      (node (ref "R21") (pin "2") (pinfunction "2_2") (pintype "passive"))
    )
    (net (code "54") (name "Net-(OK2-A)") (class "Default")
      (node (ref "OK2") (pin "1") (pinfunction "A_1") (pintype "passive"))
      (node (ref "R23") (pin "2") (pinfunction "2_2") (pintype "passive"))
    )
    (net (code "55") (name "Net-(OK3-A)") (class "Default")
      (node (ref "OK3") (pin "1") (pinfunction "A_1") (pintype "passive"))
      (node (ref "R22") (pin "2") (pinfunction "2_2") (pintype "passive"))
    )
    (net (code "56") (name "Net-(OK4-A)") (class "Default")
      (node (ref "OK4") (pin "1") (pinfunction "A_1") (pintype "passive"))
      (node (ref "R24") (pin "2") (pinfunction "2_2") (pintype "passive"))
    )
    (net (code "57") (name "PGC1") (class "Default")
      (node (ref "IC1") (pin "2") (pinfunction "RA3/AN3/C1INB/VREF+_2") (pintype "bidirectional"))
      (node (ref "J9") (pin "5") (pinfunction "S_5") (pintype "passive"))
    )
    (net (code "58") (name "PGD1") (class "Default")
      (node (ref "IC1") (pin "1") (pinfunction "RA2/AN2/C2INB/C1IND/C3INB/VREF-/CVREF_1") (pintype "bidirectional"))
      (node (ref "J9") (pin "4") (pinfunction "S_4") (pintype "passive"))
    )
    (net (code "59") (name "RX") (class "Default")
      (node (ref "FTDI") (pin "26") (pinfunction "TXD_26") (pintype "output"))
      (node (ref "IC1") (pin "4") (pinfunction "RA5/AN4/C1INC/~{SS1}/HLVDIN/RCV/RP2_4") (pintype "bidirectional"))
    )
    (net (code "60") (name "SLEEPALL") (class "Default")
      (node (ref "OK2") (pin "4") (pinfunction "COL_4") (pintype "passive"))
      (node (ref "R26") (pin "1") (pinfunction "1_1") (pintype "passive"))
    )
    (net (code "61") (name "STEP1") (class "Default")
      (node (ref "IC1") (pin "22") (pinfunction "RB4/CCP4/KBI0/SCK1/SCL1/RP7_22") (pintype "bidirectional"))
      (node (ref "U$1") (pin "7") (pinfunction "7_7") (pintype "passive"))
    )
    (net (code "62") (name "STEP2") (class "Default")
      (node (ref "IC1") (pin "19") (pinfunction "RB1/AN10/C3INC/RTCC/RP4_19") (pintype "bidirectional"))
      (node (ref "U$2") (pin "7") (pinfunction "7_7") (pintype "passive"))
    )
    (net (code "63") (name "STEP3") (class "Default")
      (node (ref "IC1") (pin "8") (pinfunction "RC0/T1OSO/T1CKI/RP11_8") (pintype "bidirectional"))
      (node (ref "U$3") (pin "7") (pinfunction "7_7") (pintype "passive"))
    )
    (net (code "64") (name "STEP4") (class "Default")
      (node (ref "IC1") (pin "6") (pinfunction "OSC1/CLKI/RA7_6") (pintype "bidirectional"))
      (node (ref "U$4") (pin "7") (pinfunction "7_7") (pintype "passive"))
    )
    (net (code "65") (name "TX") (class "Default")
      (node (ref "FTDI") (pin "25") (pinfunction "RXD_25") (pintype "input"))
      (node (ref "IC1") (pin "3") (pinfunction "VDDCORE/VCAP_3") (pintype "input"))
    )
    (net (code "66") (name "VBUS") (class "Default")
      (node (ref "BT_USB_MICROB1") (pin "VBUS") (pinfunction "VBUS_VBUS") (pintype "bidirectional"))
      (node (ref "FTDI") (pin "8") (pinfunction "VBUS_8") (pintype "input"))
      (node (ref "JP1") (pin "1") (pinfunction "1_1") (pintype "passive"))
      (node (ref "R47") (pin "2") (pinfunction "2_2") (pintype "passive"))
    )
    (net (code "67") (name "VDD") (class "Default")
      (node (ref "C29") (pin "1") (pinfunction "1_1") (pintype "passive"))
      (node (ref "C30") (pin "1") (pinfunction "1_1") (pintype "passive"))
      (node (ref "C31") (pin "1") (pinfunction "1_1") (pintype "passive"))
      (node (ref "C37") (pin "2") (pinfunction "2_2") (pintype "passive"))
      (node (ref "C38") (pin "2") (pinfunction "2_2") (pintype "passive"))
      (node (ref "C39") (pin "2") (pinfunction "2_2") (pintype "passive"))
      (node (ref "C40") (pin "2") (pinfunction "2_2") (pintype "passive"))
      (node (ref "FTDI") (pin "6") (pinfunction "VDD_6") (pintype "power_in"))
      (node (ref "FTDI") (pin "7") (pinfunction "REGIN_7") (pintype "passive"))
      (node (ref "IC1") (pin "10") (pinfunction "RC2/AN11/C2IND/CTPLS/RP13_10") (pintype "bidirectional"))
      (node (ref "IC1") (pin "25") (pinfunction "RB7/CCP7/KBI3/PGD/RP10_25") (pintype "bidirectional"))
      (node (ref "J9") (pin "2") (pinfunction "S_2") (pintype "passive"))
      (node (ref "R25") (pin "2") (pinfunction "2_2") (pintype "passive"))
      (node (ref "R26") (pin "2") (pinfunction "2_2") (pintype "passive"))
      (node (ref "R27") (pin "2") (pinfunction "2_2") (pintype "passive"))
      (node (ref "R28") (pin "2") (pinfunction "2_2") (pintype "passive"))
      (node (ref "R30") (pin "2") (pinfunction "2_2") (pintype "passive"))
      (node (ref "R46") (pin "2") (pinfunction "2_2") (pintype "passive"))
      (node (ref "U$1") (pin "6") (pinfunction "6_6") (pintype "passive"))
      (node (ref "U$2") (pin "6") (pinfunction "6_6") (pintype "passive"))
      (node (ref "U$3") (pin "6") (pinfunction "6_6") (pintype "passive"))
      (node (ref "U$4") (pin "6") (pinfunction "6_6") (pintype "passive"))
      (node (ref "U1") (pin "4") (pinfunction "VOUT_4") (pintype "power_in"))
    )
    (net (code "68") (name "VM") (class "Default")
      (node (ref "C26") (pin "+") (pinfunction "+_+") (pintype "passive"))
      (node (ref "C27") (pin "+") (pinfunction "+_+") (pintype "passive"))
      (node (ref "J5") (pin "2") (pinfunction "S_2") (pintype "passive"))
      (node (ref "J5") (pin "3") (pinfunction "S_3") (pintype "passive"))
      (node (ref "J6") (pin "2") (pinfunction "S_2") (pintype "passive"))
      (node (ref "J6") (pin "3") (pinfunction "S_3") (pintype "passive"))
      (node (ref "R4") (pin "2") (pinfunction "2_2") (pintype "passive"))
      (node (ref "R5") (pin "2") (pinfunction "2_2") (pintype "passive"))
      (node (ref "U$1") (pin "9") (pinfunction "9_9") (pintype "passive"))
      (node (ref "U$2") (pin "9") (pinfunction "9_9") (pintype "passive"))
      (node (ref "U$3") (pin "9") (pinfunction "9_9") (pintype "passive"))
      (node (ref "U$4") (pin "9") (pinfunction "9_9") (pintype "passive"))
    )
    (net (code "69") (name "VT") (class "Default")
      (node (ref "J8") (pin "1") (pinfunction "S_1") (pintype "passive"))
    )
    (net (code "70") (name "unconnected-(BT_USB_MICROB1-PadID)") (class "Default")
      (node (ref "BT_USB_MICROB1") (pin "ID") (pinfunction "ID_ID") (pintype "bidirectional"))
    )
    (net (code "71") (name "unconnected-(IC1-RA0{slash}AN0{slash}C1INA{slash}ULPWU{slash}RP0-Pad27)") (class "Default")
      (node (ref "IC1") (pin "27") (pinfunction "RA0/AN0/C1INA/ULPWU/RP0_27") (pintype "bidirectional"))
    )
    (net (code "72") (name "unconnected-(IC1-RA1{slash}AN1{slash}C2INA{slash}VBG{slash}RP1-Pad28)") (class "Default")
      (node (ref "IC1") (pin "28") (pinfunction "RA1/AN1/C2INA/VBG/RP1_28") (pintype "bidirectional"))
    )
    (net (code "73") (name "unconnected-(IC1-RB2{slash}AN8{slash}C2INC{slash}CTED1{slash}VMO{slash}REFO{slash}RP5-Pad20)") (class "Default")
      (node (ref "IC1") (pin "20") (pinfunction "RB2/AN8/C2INC/CTED1/VMO/REFO/RP5_20") (pintype "bidirectional"))
    )
    (net (code "74") (name "unconnected-(IC1-RC4{slash}D-{slash}VM-Pad12)") (class "Default")
      (node (ref "IC1") (pin "12") (pinfunction "RC4/D-/VM_12") (pintype "bidirectional"))
    )
    (net (code "75") (name "unconnected-(IC1-VDD-Pad17)") (class "Default")
      (node (ref "IC1") (pin "17") (pinfunction "VDD_17") (pintype "input"))
    )
    (net (code "76") (name "unconnected-(IC1-VSS2-Pad16)") (class "Default")
      (node (ref "IC1") (pin "16") (pinfunction "VSS2_16") (pintype "input"))
    )
    (net (code "77") (name "unconnected-(RST_JMPR-Pad1)") (class "Default")
      (node (ref "RST_JMPR") (pin "1") (pinfunction "1_1") (pintype "passive"))
    )
    (net (code "78") (name "unconnected-(U$1-Pad2)") (class "Default")
      (node (ref "U$1") (pin "2") (pinfunction "2_2") (pintype "passive"))
    )
    (net (code "79") (name "unconnected-(U$1-Pad3)") (class "Default")
      (node (ref "U$1") (pin "3") (pinfunction "3_3") (pintype "passive"))
    )
    (net (code "80") (name "unconnected-(U$1-Pad4)") (class "Default")
      (node (ref "U$1") (pin "4") (pinfunction "4_4") (pintype "passive"))
    )
    (net (code "81") (name "unconnected-(U$1-Pad5)") (class "Default")
      (node (ref "U$1") (pin "5") (pinfunction "5_5") (pintype "passive"))
    )
    (net (code "82") (name "unconnected-(U$1-Pad15)") (class "Default")
      (node (ref "U$1") (pin "15") (pinfunction "15_15") (pintype "passive"))
    )
    (net (code "83") (name "unconnected-(U$2-Pad2)") (class "Default")
      (node (ref "U$2") (pin "2") (pinfunction "2_2") (pintype "passive"))
    )
    (net (code "84") (name "unconnected-(U$2-Pad3)") (class "Default")
      (node (ref "U$2") (pin "3") (pinfunction "3_3") (pintype "passive"))
    )
    (net (code "85") (name "unconnected-(U$2-Pad4)") (class "Default")
      (node (ref "U$2") (pin "4") (pinfunction "4_4") (pintype "passive"))
    )
    (net (code "86") (name "unconnected-(U$2-Pad5)") (class "Default")
      (node (ref "U$2") (pin "5") (pinfunction "5_5") (pintype "passive"))
    )
    (net (code "87") (name "unconnected-(U$2-Pad15)") (class "Default")
      (node (ref "U$2") (pin "15") (pinfunction "15_15") (pintype "passive"))
    )
    (net (code "88") (name "unconnected-(U$3-Pad2)") (class "Default")
      (node (ref "U$3") (pin "2") (pinfunction "2_2") (pintype "passive"))
    )
    (net (code "89") (name "unconnected-(U$3-Pad3)") (class "Default")
      (node (ref "U$3") (pin "3") (pinfunction "3_3") (pintype "passive"))
    )
    (net (code "90") (name "unconnected-(U$3-Pad4)") (class "Default")
      (node (ref "U$3") (pin "4") (pinfunction "4_4") (pintype "passive"))
    )
    (net (code "91") (name "unconnected-(U$3-Pad5)") (class "Default")
      (node (ref "U$3") (pin "5") (pinfunction "5_5") (pintype "passive"))
    )
    (net (code "92") (name "unconnected-(U$3-Pad15)") (class "Default")
      (node (ref "U$3") (pin "15") (pinfunction "15_15") (pintype "passive"))
    )
    (net (code "93") (name "unconnected-(U$4-Pad2)") (class "Default")
      (node (ref "U$4") (pin "2") (pinfunction "2_2") (pintype "passive"))
    )
    (net (code "94") (name "unconnected-(U$4-Pad3)") (class "Default")
      (node (ref "U$4") (pin "3") (pinfunction "3_3") (pintype "passive"))
    )
    (net (code "95") (name "unconnected-(U$4-Pad4)") (class "Default")
      (node (ref "U$4") (pin "4") (pinfunction "4_4") (pintype "passive"))
    )
    (net (code "96") (name "unconnected-(U$4-Pad5)") (class "Default")
      (node (ref "U$4") (pin "5") (pinfunction "5_5") (pintype "passive"))
    )
    (net (code "97") (name "unconnected-(U$4-Pad15)") (class "Default")
      (node (ref "U$4") (pin "15") (pinfunction "15_15") (pintype "passive"))
    )
    (net (code "98") (name "unconnected-(U1-OUT-Pad2)") (class "Default")
      (node (ref "U1") (pin "2") (pinfunction "OUT_2") (pintype "output"))
    )
  )
)
